# BareArduino.net
KiCad netlist of a schematic drawn in EAGLE
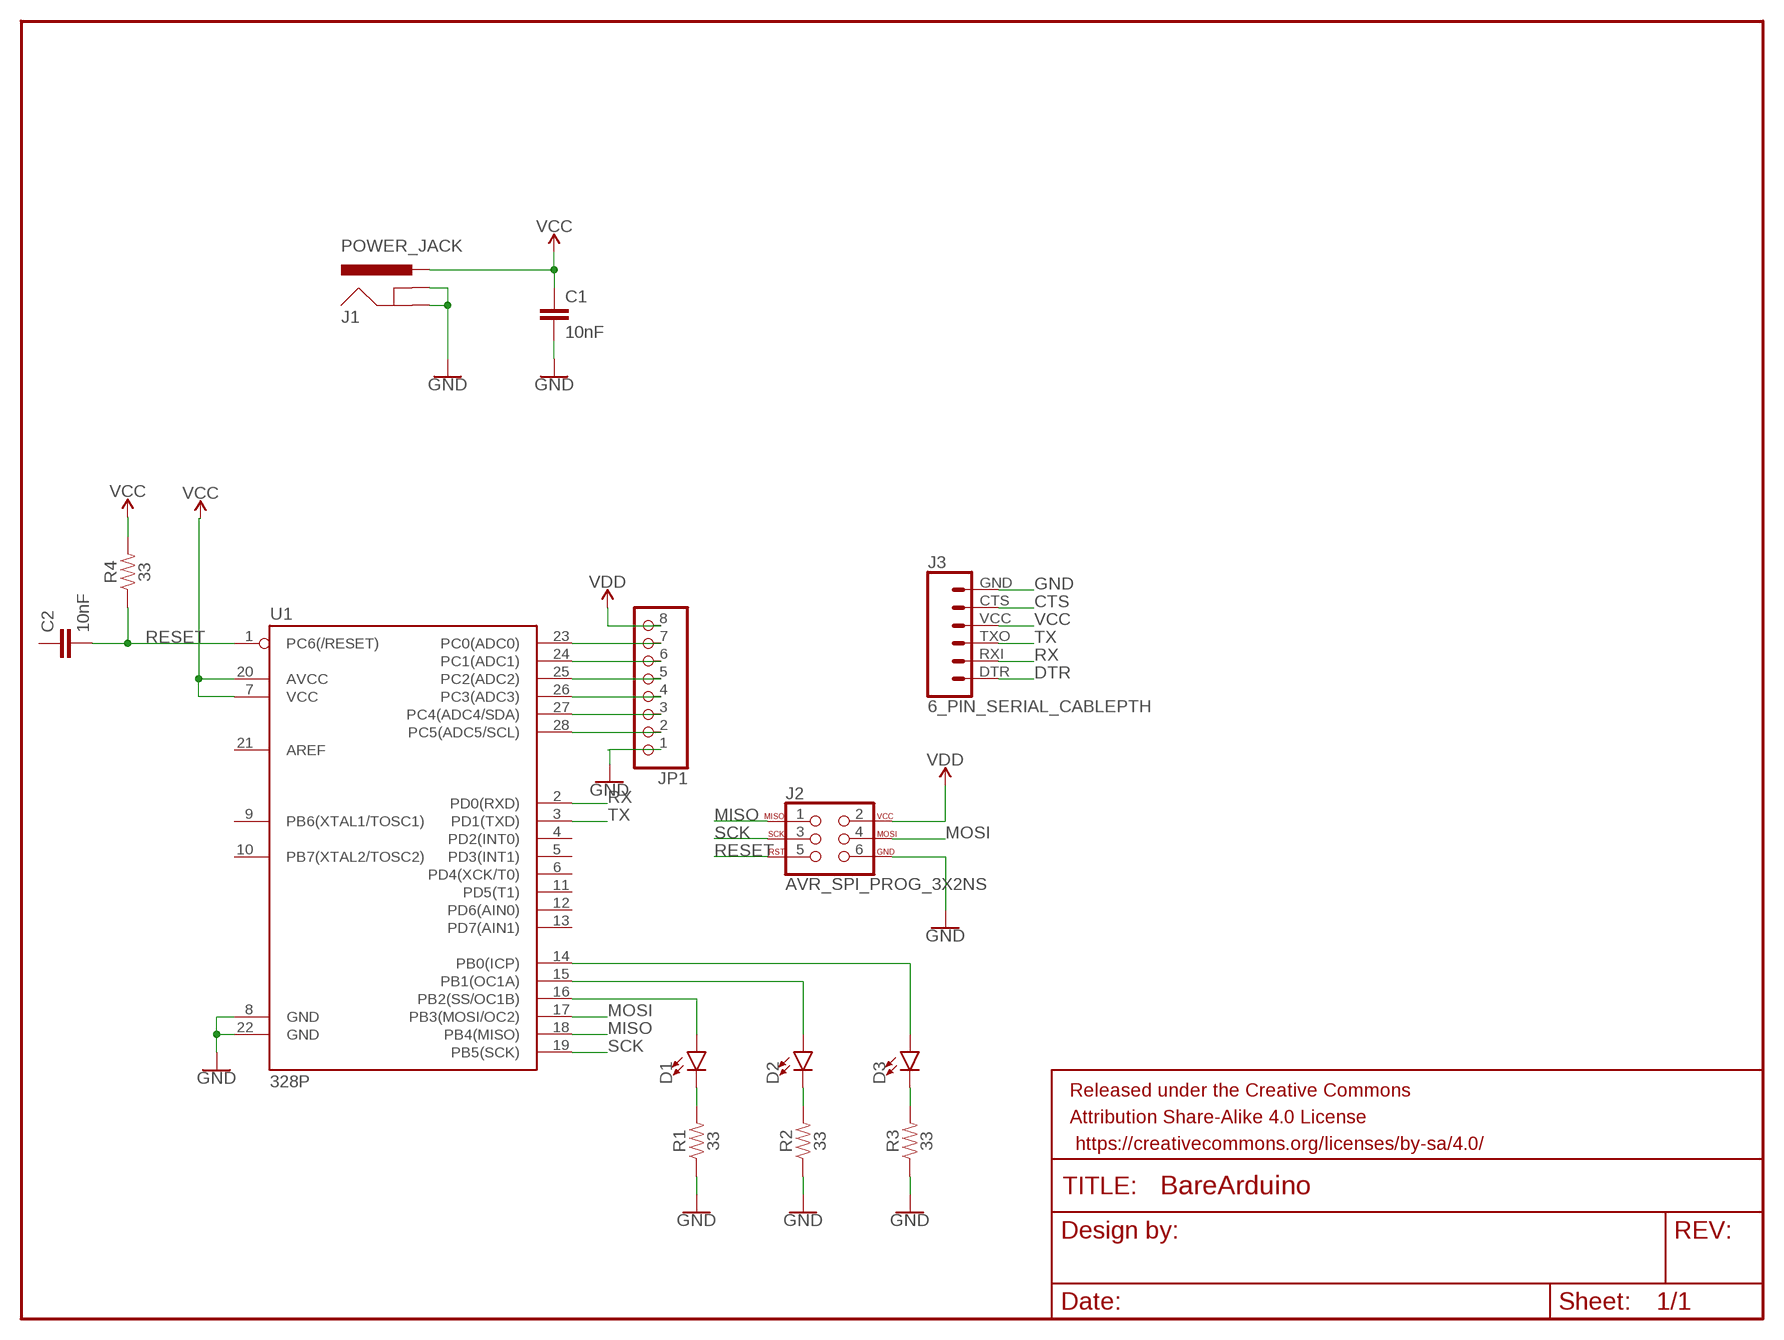
[diagram p0: schematic, sheet 1]

(export (version "E")
  (design (tool "Eeschema 10.0.6"))
  (components
    (comp (ref "C1")
      (value "10nF")
      (footprint "eagle-import:CAP-PTH-10MM")
      (libsource (lib "eagle-import") (part "10NF-PTH-10MM-10000V-1-%"))
    )
    (comp (ref "C2")
      (value "10nF")
      (footprint "eagle-import:0603")
      (libsource (lib "eagle-import") (part "10NF-0603-50V-10%"))
    )
    (comp (ref "D1")
      (value "LED5MM")
      (footprint "eagle-import:LED_5MM")
      (libsource (lib "eagle-import") (part "LED5MM"))
    )
    (comp (ref "D2")
      (value "LED5MM")
      (footprint "eagle-import:LED_5MM")
      (libsource (lib "eagle-import") (part "LED5MM"))
    )
    (comp (ref "D3")
      (value "LED5MM")
      (footprint "eagle-import:LED_5MM")
      (libsource (lib "eagle-import") (part "LED5MM"))
    )
    (comp (ref "FRAME1")
      (value "FRAME-LETTER")
      (footprint "eagle-import:CREATIVE_COMMONS")
      (libsource (lib "eagle-import") (part "FRAME-LETTER"))
    )
    (comp (ref "J1")
      (value "POWER_JACK")
      (footprint "eagle-import:POWER_JACK_PTH")
      (libsource (lib "eagle-import") (part "POWER_JACK"))
    )
    (comp (ref "J2")
      (value "AVR_SPI_PROG_3X2NS")
      (footprint "eagle-import:2X3-NS")
      (libsource (lib "eagle-import") (part "AVR_SPI_PROG_3X2NS"))
    )
    (comp (ref "J3")
      (value "6_PIN_SERIAL_CABLEPTH")
      (footprint "eagle-import:FTDI_BASIC")
      (libsource (lib "eagle-import") (part "6_PIN_SERIAL_CABLEPTH"))
    )
    (comp (ref "JP1")
      (value "PINHD-1X8")
      (footprint "eagle-import:1X08")
      (libsource (lib "eagle-import") (part "PINHD-1X8"))
    )
    (comp (ref "R1")
      (value "33")
      (footprint "eagle-import:0603")
      (libsource (lib "eagle-import") (part "33OHM-0603-1/10W-1%"))
    )
    (comp (ref "R2")
      (value "33")
      (footprint "eagle-import:0603")
      (libsource (lib "eagle-import") (part "33OHM-0603-1/10W-1%"))
    )
    (comp (ref "R3")
      (value "33")
      (footprint "eagle-import:0603")
      (libsource (lib "eagle-import") (part "33OHM-0603-1/10W-1%"))
    )
    (comp (ref "R4")
      (value "33")
      (footprint "eagle-import:0603")
      (libsource (lib "eagle-import") (part "33OHM-0603-1/10W-1%"))
    )
    (comp (ref "U1")
      (value "328P")
      (footprint "eagle-import:DIP28")
      (libsource (lib "eagle-import") (part "ATMEGA328P_PDIP"))
    )
  )
  (nets
    (net (code "1") (name "/CTS") (class "Default")
      (node (ref "J3") (pin "CTS") (pinfunction "5_CTS") (pintype "passive"))
    )
    (net (code "2") (name "/DTR") (class "Default")
      (node (ref "J3") (pin "DTR") (pinfunction "1_DTR") (pintype "passive"))
    )
    (net (code "3") (name "/MISO") (class "Default")
      (node (ref "J2") (pin "1") (pinfunction "1_1") (pintype "passive"))
      (node (ref "U1") (pin "18") (pinfunction "PB4(MISO)_18") (pintype "bidirectional"))
    )
    (net (code "4") (name "/MOSI") (class "Default")
      (node (ref "J2") (pin "4") (pinfunction "4_4") (pintype "passive"))
      (node (ref "U1") (pin "17") (pinfunction "PB3(MOSI/OC2)_17") (pintype "bidirectional"))
    )
    (net (code "5") (name "/RESET") (class "Default")
      (node (ref "C2") (pin "2") (pinfunction "2_2") (pintype "passive"))
      (node (ref "J2") (pin "5") (pinfunction "5_5") (pintype "passive"))
      (node (ref "R4") (pin "1") (pinfunction "1_1") (pintype "passive"))
      (node (ref "U1") (pin "1") (pinfunction "PC6(/RESET)_1") (pintype "bidirectional"))
    )
    (net (code "6") (name "/RX") (class "Default")
      (node (ref "J3") (pin "RXI") (pinfunction "2_RXI") (pintype "passive"))
      (node (ref "U1") (pin "2") (pinfunction "PD0(RXD)_2") (pintype "bidirectional"))
    )
    (net (code "7") (name "/SCK") (class "Default")
      (node (ref "J2") (pin "3") (pinfunction "3_3") (pintype "passive"))
      (node (ref "U1") (pin "19") (pinfunction "PB5(SCK)_19") (pintype "bidirectional"))
    )
    (net (code "8") (name "/TX") (class "Default")
      (node (ref "J3") (pin "TXO") (pinfunction "3_TXO") (pintype "passive"))
      (node (ref "U1") (pin "3") (pinfunction "PD1(TXD)_3") (pintype "bidirectional"))
    )
    (net (code "9") (name "GND") (class "Default")
      (node (ref "C1") (pin "2") (pinfunction "2_2") (pintype "passive"))
      (node (ref "J1") (pin "GND") (pinfunction "GND_GND") (pintype "bidirectional"))
      (node (ref "J1") (pin "GNDBREAK") (pinfunction "GNDBREAK_GNDBREAK") (pintype "bidirectional"))
      (node (ref "J2") (pin "6") (pinfunction "6_6") (pintype "passive"))
      (node (ref "J3") (pin "GND") (pinfunction "6_GND") (pintype "passive"))
      (node (ref "JP1") (pin "1") (pinfunction "1_1") (pintype "passive"))
      (node (ref "R1") (pin "1") (pinfunction "1_1") (pintype "passive"))
      (node (ref "R2") (pin "1") (pinfunction "1_1") (pintype "passive"))
      (node (ref "R3") (pin "1") (pinfunction "1_1") (pintype "passive"))
      (node (ref "U1") (pin "22") (pinfunction "GND_22") (pintype "bidirectional"))
      (node (ref "U1") (pin "8") (pinfunction "GND_8") (pintype "bidirectional"))
    )
    (net (code "10") (name "Net-(D1-C)") (class "Default")
      (node (ref "D1") (pin "K") (pinfunction "C_K") (pintype "passive"))
      (node (ref "R1") (pin "2") (pinfunction "2_2") (pintype "passive"))
    )
    (net (code "11") (name "Net-(D2-C)") (class "Default")
      (node (ref "D2") (pin "K") (pinfunction "C_K") (pintype "passive"))
      (node (ref "R2") (pin "2") (pinfunction "2_2") (pintype "passive"))
    )
    (net (code "12") (name "Net-(D3-C)") (class "Default")
      (node (ref "D3") (pin "K") (pinfunction "C_K") (pintype "passive"))
      (node (ref "R3") (pin "2") (pinfunction "2_2") (pintype "passive"))
    )
    (net (code "13") (name "Net-(U1-PB0(ICP))") (class "Default")
      (node (ref "D3") (pin "A") (pinfunction "A_A") (pintype "passive"))
      (node (ref "U1") (pin "14") (pinfunction "PB0(ICP)_14") (pintype "bidirectional"))
    )
    (net (code "14") (name "Net-(U1-PB1(OC1A))") (class "Default")
      (node (ref "D2") (pin "A") (pinfunction "A_A") (pintype "passive"))
      (node (ref "U1") (pin "15") (pinfunction "PB1(OC1A)_15") (pintype "bidirectional"))
    )
    (net (code "15") (name "Net-(U1-PB2(SS{slash}OC1B))") (class "Default")
      (node (ref "D1") (pin "A") (pinfunction "A_A") (pintype "passive"))
      (node (ref "U1") (pin "16") (pinfunction "PB2(SS/OC1B)_16") (pintype "bidirectional"))
    )
    (net (code "16") (name "Net-(U1-PC0(ADC0))") (class "Default")
      (node (ref "JP1") (pin "7") (pinfunction "7_7") (pintype "passive"))
      (node (ref "U1") (pin "23") (pinfunction "PC0(ADC0)_23") (pintype "bidirectional"))
    )
    (net (code "17") (name "Net-(U1-PC1(ADC1))") (class "Default")
      (node (ref "JP1") (pin "6") (pinfunction "6_6") (pintype "passive"))
      (node (ref "U1") (pin "24") (pinfunction "PC1(ADC1)_24") (pintype "bidirectional"))
    )
    (net (code "18") (name "Net-(U1-PC2(ADC2))") (class "Default")
      (node (ref "JP1") (pin "5") (pinfunction "5_5") (pintype "passive"))
      (node (ref "U1") (pin "25") (pinfunction "PC2(ADC2)_25") (pintype "bidirectional"))
    )
    (net (code "19") (name "Net-(U1-PC3(ADC3))") (class "Default")
      (node (ref "JP1") (pin "4") (pinfunction "4_4") (pintype "passive"))
      (node (ref "U1") (pin "26") (pinfunction "PC3(ADC3)_26") (pintype "bidirectional"))
    )
    (net (code "20") (name "Net-(U1-PC4(ADC4{slash}SDA))") (class "Default")
      (node (ref "JP1") (pin "3") (pinfunction "3_3") (pintype "passive"))
      (node (ref "U1") (pin "27") (pinfunction "PC4(ADC4/SDA)_27") (pintype "bidirectional"))
    )
    (net (code "21") (name "Net-(U1-PC5(ADC5{slash}SCL))") (class "Default")
      (node (ref "JP1") (pin "2") (pinfunction "2_2") (pintype "passive"))
      (node (ref "U1") (pin "28") (pinfunction "PC5(ADC5/SCL)_28") (pintype "bidirectional"))
    )
    (net (code "22") (name "VCC") (class "Default")
      (node (ref "C1") (pin "1") (pinfunction "1_1") (pintype "passive"))
      (node (ref "J1") (pin "PWR") (pinfunction "PWR_PWR") (pintype "bidirectional"))
      (node (ref "J3") (pin "VCC") (pinfunction "4_VCC") (pintype "passive"))
      (node (ref "R4") (pin "2") (pinfunction "2_2") (pintype "passive"))
      (node (ref "U1") (pin "20") (pinfunction "AVCC_20") (pintype "bidirectional"))
      (node (ref "U1") (pin "7") (pinfunction "VCC_7") (pintype "bidirectional"))
    )
    (net (code "23") (name "VDD") (class "Default")
      (node (ref "J2") (pin "2") (pinfunction "2_2") (pintype "passive"))
      (node (ref "JP1") (pin "8") (pinfunction "8_8") (pintype "passive"))
    )
    (net (code "24") (name "unconnected-(C2-Pad1)") (class "Default")
      (node (ref "C2") (pin "1") (pinfunction "1_1") (pintype "passive"))
    )
    (net (code "25") (name "unconnected-(U1-AREF-Pad21)") (class "Default")
      (node (ref "U1") (pin "21") (pinfunction "AREF_21") (pintype "bidirectional"))
    )
    (net (code "26") (name "unconnected-(U1-PB6(XTAL1{slash}TOSC1)-Pad9)") (class "Default")
      (node (ref "U1") (pin "9") (pinfunction "PB6(XTAL1/TOSC1)_9") (pintype "bidirectional"))
    )
    (net (code "27") (name "unconnected-(U1-PB7(XTAL2{slash}TOSC2)-Pad10)") (class "Default")
      (node (ref "U1") (pin "10") (pinfunction "PB7(XTAL2/TOSC2)_10") (pintype "bidirectional"))
    )
    (net (code "28") (name "unconnected-(U1-PD2(INT0)-Pad4)") (class "Default")
      (node (ref "U1") (pin "4") (pinfunction "PD2(INT0)_4") (pintype "bidirectional"))
    )
    (net (code "29") (name "unconnected-(U1-PD3(INT1)-Pad5)") (class "Default")
      (node (ref "U1") (pin "5") (pinfunction "PD3(INT1)_5") (pintype "bidirectional"))
    )
    (net (code "30") (name "unconnected-(U1-PD4(XCK{slash}T0)-Pad6)") (class "Default")
      (node (ref "U1") (pin "6") (pinfunction "PD4(XCK/T0)_6") (pintype "bidirectional"))
    )
    (net (code "31") (name "unconnected-(U1-PD5(T1)-Pad11)") (class "Default")
      (node (ref "U1") (pin "11") (pinfunction "PD5(T1)_11") (pintype "bidirectional"))
    )
    (net (code "32") (name "unconnected-(U1-PD6(AIN0)-Pad12)") (class "Default")
      (node (ref "U1") (pin "12") (pinfunction "PD6(AIN0)_12") (pintype "bidirectional"))
    )
    (net (code "33") (name "unconnected-(U1-PD7(AIN1)-Pad13)") (class "Default")
      (node (ref "U1") (pin "13") (pinfunction "PD7(AIN1)_13") (pintype "bidirectional"))
    )
  )
)
